# ValveModule_r1.net
KiCad netlist of a schematic drawn in EAGLE
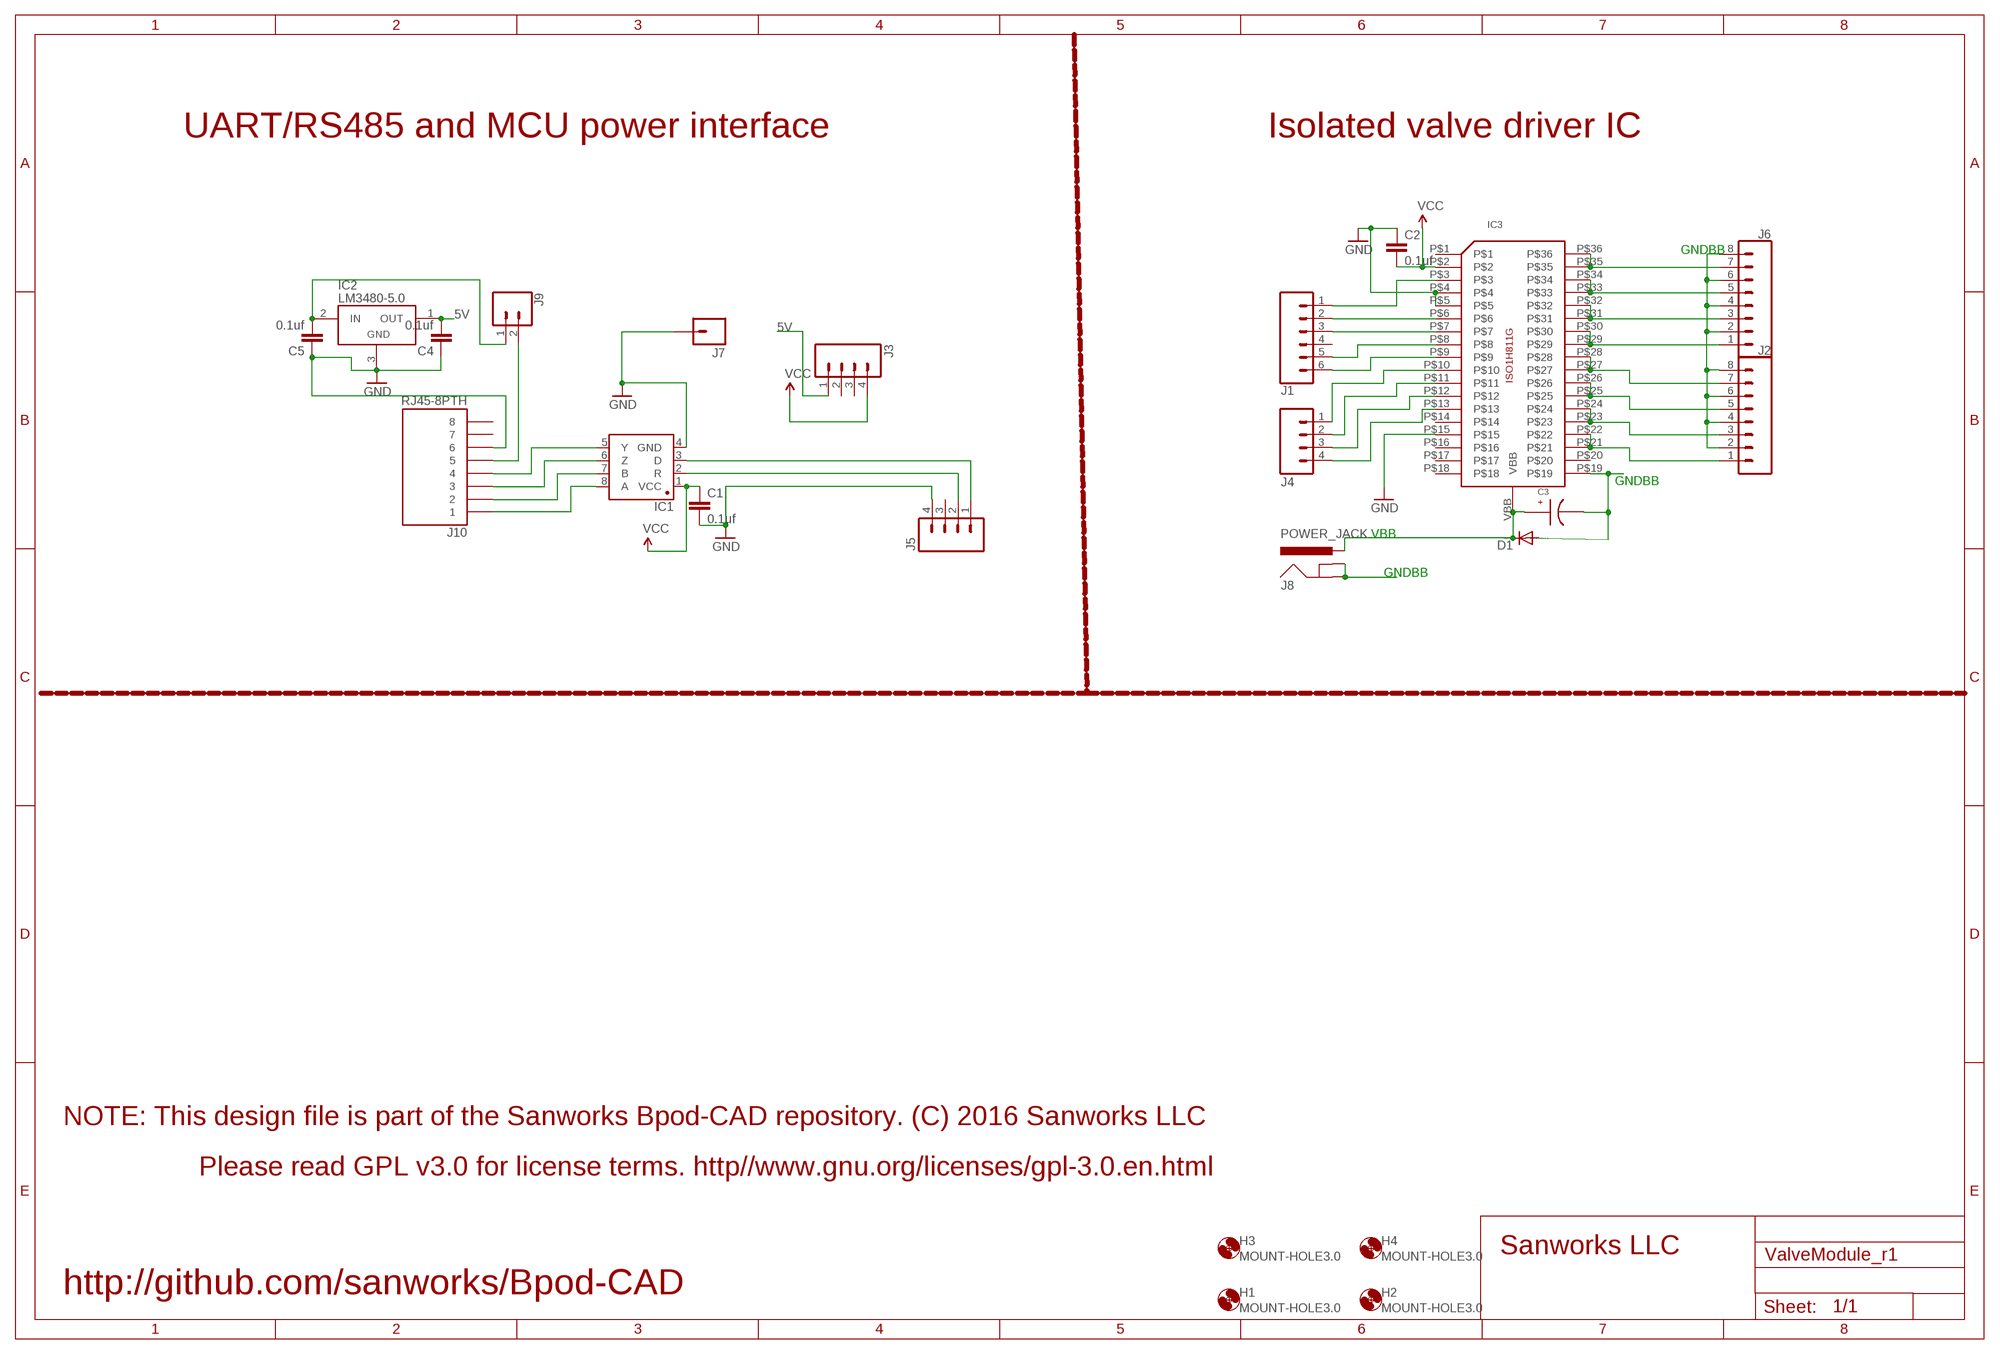
[diagram p0: schematic, sheet 1]

(export (version "E")
  (design (tool "Eeschema 10.0.6"))
  (components
    (comp (ref "C1")
      (value "0.1uf")
      (footprint "eagle-import:1206")
      (libsource (lib "eagle-import") (part "CAP1206"))
    )
    (comp (ref "C2")
      (value "0.1uf")
      (footprint "eagle-import:1206")
      (libsource (lib "eagle-import") (part "CAP1206"))
    )
    (comp (ref "C3")
      (value "EEE-FK1H100UR")
      (footprint "eagle-import:EEE-FK1H100UR")
      (libsource (lib "eagle-import") (part "EEE-FK1H100UR"))
    )
    (comp (ref "C4")
      (value "0.1uf")
      (footprint "eagle-import:1206")
      (libsource (lib "eagle-import") (part "CAP1206"))
    )
    (comp (ref "C5")
      (value "0.1uf")
      (footprint "eagle-import:1206")
      (libsource (lib "eagle-import") (part "CAP1206"))
    )
    (comp (ref "D1")
      (value "DIODE-DO214AA")
      (footprint "eagle-import:DO214AA")
      (libsource (lib "eagle-import") (part "DIODE-DO214AA"))
    )
    (comp (ref "H1")
      (value "MOUNT-HOLE3.0")
      (footprint "eagle-import:3,0")
      (libsource (lib "eagle-import") (part "MOUNT-HOLE3.0"))
    )
    (comp (ref "H2")
      (value "MOUNT-HOLE3.0")
      (footprint "eagle-import:3,0")
      (libsource (lib "eagle-import") (part "MOUNT-HOLE3.0"))
    )
    (comp (ref "H3")
      (value "MOUNT-HOLE3.0")
      (footprint "eagle-import:3,0")
      (libsource (lib "eagle-import") (part "MOUNT-HOLE3.0"))
    )
    (comp (ref "H4")
      (value "MOUNT-HOLE3.0")
      (footprint "eagle-import:3,0")
      (libsource (lib "eagle-import") (part "MOUNT-HOLE3.0"))
    )
    (comp (ref "IC1")
      (value "SN65HVD31DR")
      (footprint "eagle-import:SO08")
      (libsource (lib "eagle-import") (part "SN65HVD31DR"))
    )
    (comp (ref "IC2")
      (value "LM3480-5.0")
      (footprint "eagle-import:SOT-23-3")
      (libsource (lib "eagle-import") (part "LM3480-5.0"))
    )
    (comp (ref "IC3")
      (value "ISO1H811G")
      (footprint "eagle-import:ISO1H811G")
      (libsource (lib "eagle-import") (part "ISO1H811G"))
    )
    (comp (ref "J1")
      (value "CONN_06SILK_FEMALE_PTH")
      (footprint "eagle-import:1X06")
      (libsource (lib "eagle-import") (part "CONN_06SILK_FEMALE_PTH"))
    )
    (comp (ref "J2")
      (value "CONN_083.5MM-8")
      (footprint "eagle-import:SCREWTERMINAL-3.5MM-8")
      (libsource (lib "eagle-import") (part "CONN_083.5MM-8"))
    )
    (comp (ref "J3")
      (value "M04PTH")
      (footprint "eagle-import:1X04")
      (libsource (lib "eagle-import") (part "M04PTH"))
    )
    (comp (ref "J4")
      (value "M04PTH")
      (footprint "eagle-import:1X04")
      (libsource (lib "eagle-import") (part "M04PTH"))
    )
    (comp (ref "J5")
      (value "M04PTH")
      (footprint "eagle-import:1X04")
      (libsource (lib "eagle-import") (part "M04PTH"))
    )
    (comp (ref "J6")
      (value "CONN_083.5MM-8")
      (footprint "eagle-import:SCREWTERMINAL-3.5MM-8")
      (libsource (lib "eagle-import") (part "CONN_083.5MM-8"))
    )
    (comp (ref "J7")
      (value "M01PTH")
      (footprint "eagle-import:1X01")
      (libsource (lib "eagle-import") (part "M01PTH"))
    )
    (comp (ref "J8")
      (value "POWER_JACK")
      (footprint "eagle-import:POWER_JACK_PTH")
      (libsource (lib "eagle-import") (part "POWER_JACK"))
    )
    (comp (ref "J9")
      (value "CONN_02")
      (footprint "eagle-import:1X02")
      (libsource (lib "eagle-import") (part "CONN_02"))
    )
    (comp (ref "J10")
      (value "RJ45-8PTH")
      (footprint "eagle-import:RJ45-8")
      (libsource (lib "eagle-import") (part "RJ45-8PTH"))
    )
  )
  (nets
    (net (code "1") (name "/5V") (class "Default")
      (node (ref "C4") (pin "2") (pinfunction "2_2") (pintype "passive"))
      (node (ref "IC2") (pin "1") (pinfunction "OUT_1") (pintype "power_in"))
      (node (ref "J3") (pin "1") (pinfunction "1_1") (pintype "passive"))
    )
    (net (code "2") (name "/GNDBB") (class "Default")
      (node (ref "C3") (pin "CATHODE") (pinfunction "CATHODE_CATHODE") (pintype "bidirectional"))
      (node (ref "D1") (pin "A") (pinfunction "A_A") (pintype "passive"))
      (node (ref "IC3") (pin "P$19") (pinfunction "P$19_P$19") (pintype "bidirectional"))
      (node (ref "J2") (pin "2") (pinfunction "2_2") (pintype "passive"))
      (node (ref "J2") (pin "4") (pinfunction "4_4") (pintype "passive"))
      (node (ref "J2") (pin "6") (pinfunction "6_6") (pintype "passive"))
      (node (ref "J2") (pin "8") (pinfunction "8_8") (pintype "passive"))
      (node (ref "J6") (pin "2") (pinfunction "2_2") (pintype "passive"))
      (node (ref "J6") (pin "4") (pinfunction "4_4") (pintype "passive"))
      (node (ref "J6") (pin "6") (pinfunction "6_6") (pintype "passive"))
      (node (ref "J6") (pin "8") (pinfunction "8_8") (pintype "passive"))
      (node (ref "J8") (pin "GND") (pinfunction "GND_GND") (pintype "bidirectional"))
      (node (ref "J8") (pin "GNDBREAK") (pinfunction "GNDBREAK_GNDBREAK") (pintype "bidirectional"))
    )
    (net (code "3") (name "GND") (class "Default")
      (node (ref "C1") (pin "2") (pinfunction "2_2") (pintype "passive"))
      (node (ref "C2") (pin "1") (pinfunction "1_1") (pintype "passive"))
      (node (ref "C4") (pin "1") (pinfunction "1_1") (pintype "passive"))
      (node (ref "C5") (pin "1") (pinfunction "1_1") (pintype "passive"))
      (node (ref "IC1") (pin "4") (pinfunction "GND_4") (pintype "bidirectional"))
      (node (ref "IC2") (pin "3") (pinfunction "GND_3") (pintype "power_in"))
      (node (ref "IC3") (pin "P$15") (pinfunction "P$15_P$15") (pintype "bidirectional"))
      (node (ref "IC3") (pin "P$4") (pinfunction "P$4_P$4") (pintype "bidirectional"))
      (node (ref "IC3") (pin "P$5") (pinfunction "P$5_P$5") (pintype "bidirectional"))
      (node (ref "J10") (pin "6") (pinfunction "6_6") (pintype "bidirectional"))
      (node (ref "J5") (pin "4") (pinfunction "4_4") (pintype "passive"))
      (node (ref "J7") (pin "1") (pinfunction "1_1") (pintype "passive"))
    )
    (net (code "4") (name "Net-(C3-PadANODE)") (class "Default")
      (node (ref "C3") (pin "ANODE") (pinfunction "ANODE_ANODE") (pintype "bidirectional"))
      (node (ref "D1") (pin "C") (pinfunction "C_C") (pintype "passive"))
      (node (ref "IC3") (pin "VBB") (pinfunction "VBB_VBB") (pintype "bidirectional"))
      (node (ref "J8") (pin "PWR") (pinfunction "PWR_PWR") (pintype "bidirectional"))
    )
    (net (code "5") (name "Net-(IC1-A)") (class "Default")
      (node (ref "IC1") (pin "8") (pinfunction "A_8") (pintype "bidirectional"))
      (node (ref "J10") (pin "1") (pinfunction "1_1") (pintype "bidirectional"))
    )
    (net (code "6") (name "Net-(IC1-B)") (class "Default")
      (node (ref "IC1") (pin "7") (pinfunction "B_7") (pintype "bidirectional"))
      (node (ref "J10") (pin "2") (pinfunction "2_2") (pintype "bidirectional"))
    )
    (net (code "7") (name "Net-(IC1-D)") (class "Default")
      (node (ref "IC1") (pin "3") (pinfunction "D_3") (pintype "bidirectional"))
      (node (ref "J5") (pin "1") (pinfunction "1_1") (pintype "passive"))
    )
    (net (code "8") (name "Net-(IC1-R)") (class "Default")
      (node (ref "IC1") (pin "2") (pinfunction "R_2") (pintype "bidirectional"))
      (node (ref "J5") (pin "2") (pinfunction "2_2") (pintype "passive"))
    )
    (net (code "9") (name "Net-(IC1-Y)") (class "Default")
      (node (ref "IC1") (pin "5") (pinfunction "Y_5") (pintype "bidirectional"))
      (node (ref "J10") (pin "4") (pinfunction "4_4") (pintype "bidirectional"))
    )
    (net (code "10") (name "Net-(IC1-Z)") (class "Default")
      (node (ref "IC1") (pin "6") (pinfunction "Z_6") (pintype "bidirectional"))
      (node (ref "J10") (pin "3") (pinfunction "3_3") (pintype "bidirectional"))
    )
    (net (code "11") (name "Net-(IC2-IN)") (class "Default")
      (node (ref "C5") (pin "2") (pinfunction "2_2") (pintype "passive"))
      (node (ref "IC2") (pin "2") (pinfunction "IN_2") (pintype "power_in"))
      (node (ref "J9") (pin "1") (pinfunction "1_1") (pintype "passive"))
    )
    (net (code "12") (name "Net-(IC3-PadP$3)") (class "Default")
      (node (ref "IC3") (pin "P$3") (pinfunction "P$3_P$3") (pintype "bidirectional"))
      (node (ref "J1") (pin "1") (pinfunction "1_1") (pintype "passive"))
    )
    (net (code "13") (name "Net-(IC3-PadP$6)") (class "Default")
      (node (ref "IC3") (pin "P$6") (pinfunction "P$6_P$6") (pintype "bidirectional"))
      (node (ref "J1") (pin "2") (pinfunction "2_2") (pintype "passive"))
    )
    (net (code "14") (name "Net-(IC3-PadP$7)") (class "Default")
      (node (ref "IC3") (pin "P$7") (pinfunction "P$7_P$7") (pintype "bidirectional"))
      (node (ref "J1") (pin "3") (pinfunction "3_3") (pintype "passive"))
    )
    (net (code "15") (name "Net-(IC3-PadP$8)") (class "Default")
      (node (ref "IC3") (pin "P$8") (pinfunction "P$8_P$8") (pintype "bidirectional"))
      (node (ref "J1") (pin "5") (pinfunction "5_5") (pintype "passive"))
    )
    (net (code "16") (name "Net-(IC3-PadP$9)") (class "Default")
      (node (ref "IC3") (pin "P$9") (pinfunction "P$9_P$9") (pintype "bidirectional"))
      (node (ref "J1") (pin "6") (pinfunction "6_6") (pintype "passive"))
    )
    (net (code "17") (name "Net-(IC3-PadP$10)") (class "Default")
      (node (ref "IC3") (pin "P$10") (pinfunction "P$10_P$10") (pintype "bidirectional"))
      (node (ref "J4") (pin "1") (pinfunction "1_1") (pintype "passive"))
    )
    (net (code "18") (name "Net-(IC3-PadP$11)") (class "Default")
      (node (ref "IC3") (pin "P$11") (pinfunction "P$11_P$11") (pintype "bidirectional"))
      (node (ref "J4") (pin "2") (pinfunction "2_2") (pintype "passive"))
    )
    (net (code "19") (name "Net-(IC3-PadP$12)") (class "Default")
      (node (ref "IC3") (pin "P$12") (pinfunction "P$12_P$12") (pintype "bidirectional"))
      (node (ref "J4") (pin "3") (pinfunction "3_3") (pintype "passive"))
    )
    (net (code "20") (name "Net-(IC3-PadP$13)") (class "Default")
      (node (ref "IC3") (pin "P$13") (pinfunction "P$13_P$13") (pintype "bidirectional"))
      (node (ref "J4") (pin "4") (pinfunction "4_4") (pintype "passive"))
    )
    (net (code "21") (name "Net-(IC3-PadP$21)") (class "Default")
      (node (ref "IC3") (pin "P$21") (pinfunction "P$21_P$21") (pintype "bidirectional"))
      (node (ref "IC3") (pin "P$22") (pinfunction "P$22_P$22") (pintype "bidirectional"))
      (node (ref "J2") (pin "1") (pinfunction "1_1") (pintype "passive"))
    )
    (net (code "22") (name "Net-(IC3-PadP$23)") (class "Default")
      (node (ref "IC3") (pin "P$23") (pinfunction "P$23_P$23") (pintype "bidirectional"))
      (node (ref "IC3") (pin "P$24") (pinfunction "P$24_P$24") (pintype "bidirectional"))
      (node (ref "J2") (pin "3") (pinfunction "3_3") (pintype "passive"))
    )
    (net (code "23") (name "Net-(IC3-PadP$25)") (class "Default")
      (node (ref "IC3") (pin "P$25") (pinfunction "P$25_P$25") (pintype "bidirectional"))
      (node (ref "IC3") (pin "P$26") (pinfunction "P$26_P$26") (pintype "bidirectional"))
      (node (ref "J2") (pin "5") (pinfunction "5_5") (pintype "passive"))
    )
    (net (code "24") (name "Net-(IC3-PadP$27)") (class "Default")
      (node (ref "IC3") (pin "P$27") (pinfunction "P$27_P$27") (pintype "bidirectional"))
      (node (ref "IC3") (pin "P$28") (pinfunction "P$28_P$28") (pintype "bidirectional"))
      (node (ref "J2") (pin "7") (pinfunction "7_7") (pintype "passive"))
    )
    (net (code "25") (name "Net-(IC3-PadP$29)") (class "Default")
      (node (ref "IC3") (pin "P$29") (pinfunction "P$29_P$29") (pintype "bidirectional"))
      (node (ref "IC3") (pin "P$30") (pinfunction "P$30_P$30") (pintype "bidirectional"))
      (node (ref "J6") (pin "1") (pinfunction "1_1") (pintype "passive"))
    )
    (net (code "26") (name "Net-(IC3-PadP$31)") (class "Default")
      (node (ref "IC3") (pin "P$31") (pinfunction "P$31_P$31") (pintype "bidirectional"))
      (node (ref "IC3") (pin "P$32") (pinfunction "P$32_P$32") (pintype "bidirectional"))
      (node (ref "J6") (pin "3") (pinfunction "3_3") (pintype "passive"))
    )
    (net (code "27") (name "Net-(IC3-PadP$33)") (class "Default")
      (node (ref "IC3") (pin "P$33") (pinfunction "P$33_P$33") (pintype "bidirectional"))
      (node (ref "IC3") (pin "P$34") (pinfunction "P$34_P$34") (pintype "bidirectional"))
      (node (ref "J6") (pin "5") (pinfunction "5_5") (pintype "passive"))
    )
    (net (code "28") (name "Net-(IC3-PadP$35)") (class "Default")
      (node (ref "IC3") (pin "P$35") (pinfunction "P$35_P$35") (pintype "bidirectional"))
      (node (ref "IC3") (pin "P$36") (pinfunction "P$36_P$36") (pintype "bidirectional"))
      (node (ref "J6") (pin "7") (pinfunction "7_7") (pintype "passive"))
    )
    (net (code "29") (name "Net-(J10-Pad5)") (class "Default")
      (node (ref "J10") (pin "5") (pinfunction "5_5") (pintype "bidirectional"))
      (node (ref "J9") (pin "2") (pinfunction "2_2") (pintype "passive"))
    )
    (net (code "30") (name "VCC") (class "Default")
      (node (ref "C1") (pin "1") (pinfunction "1_1") (pintype "passive"))
      (node (ref "C2") (pin "2") (pinfunction "2_2") (pintype "passive"))
      (node (ref "IC1") (pin "1") (pinfunction "VCC_1") (pintype "bidirectional"))
      (node (ref "IC3") (pin "P$2") (pinfunction "P$2_P$2") (pintype "bidirectional"))
      (node (ref "J3") (pin "4") (pinfunction "4_4") (pintype "passive"))
    )
    (net (code "31") (name "unconnected-(IC3-PadP$1)") (class "Default")
      (node (ref "IC3") (pin "P$1") (pinfunction "P$1_P$1") (pintype "bidirectional"))
    )
    (net (code "32") (name "unconnected-(IC3-PadP$14)") (class "Default")
      (node (ref "IC3") (pin "P$14") (pinfunction "P$14_P$14") (pintype "bidirectional"))
    )
    (net (code "33") (name "unconnected-(IC3-PadP$16)") (class "Default")
      (node (ref "IC3") (pin "P$16") (pinfunction "P$16_P$16") (pintype "bidirectional"))
    )
    (net (code "34") (name "unconnected-(IC3-PadP$17)") (class "Default")
      (node (ref "IC3") (pin "P$17") (pinfunction "P$17_P$17") (pintype "bidirectional"))
    )
    (net (code "35") (name "unconnected-(IC3-PadP$18)") (class "Default")
      (node (ref "IC3") (pin "P$18") (pinfunction "P$18_P$18") (pintype "bidirectional"))
    )
    (net (code "36") (name "unconnected-(IC3-PadP$20)") (class "Default")
      (node (ref "IC3") (pin "P$20") (pinfunction "P$20_P$20") (pintype "bidirectional"))
    )
    (net (code "37") (name "unconnected-(J1-Pad4)") (class "Default")
      (node (ref "J1") (pin "4") (pinfunction "4_4") (pintype "passive"))
    )
    (net (code "38") (name "unconnected-(J3-Pad2)") (class "Default")
      (node (ref "J3") (pin "2") (pinfunction "2_2") (pintype "passive"))
    )
    (net (code "39") (name "unconnected-(J3-Pad3)") (class "Default")
      (node (ref "J3") (pin "3") (pinfunction "3_3") (pintype "passive"))
    )
    (net (code "40") (name "unconnected-(J5-Pad3)") (class "Default")
      (node (ref "J5") (pin "3") (pinfunction "3_3") (pintype "passive"))
    )
    (net (code "41") (name "unconnected-(J10-Pad7)") (class "Default")
      (node (ref "J10") (pin "7") (pinfunction "7_7") (pintype "bidirectional"))
    )
    (net (code "42") (name "unconnected-(J10-Pad8)") (class "Default")
      (node (ref "J10") (pin "8") (pinfunction "8_8") (pintype "bidirectional"))
    )
  )
)
